# 164_001_01B-v2.net
KiCad netlist of a schematic drawn in EAGLE
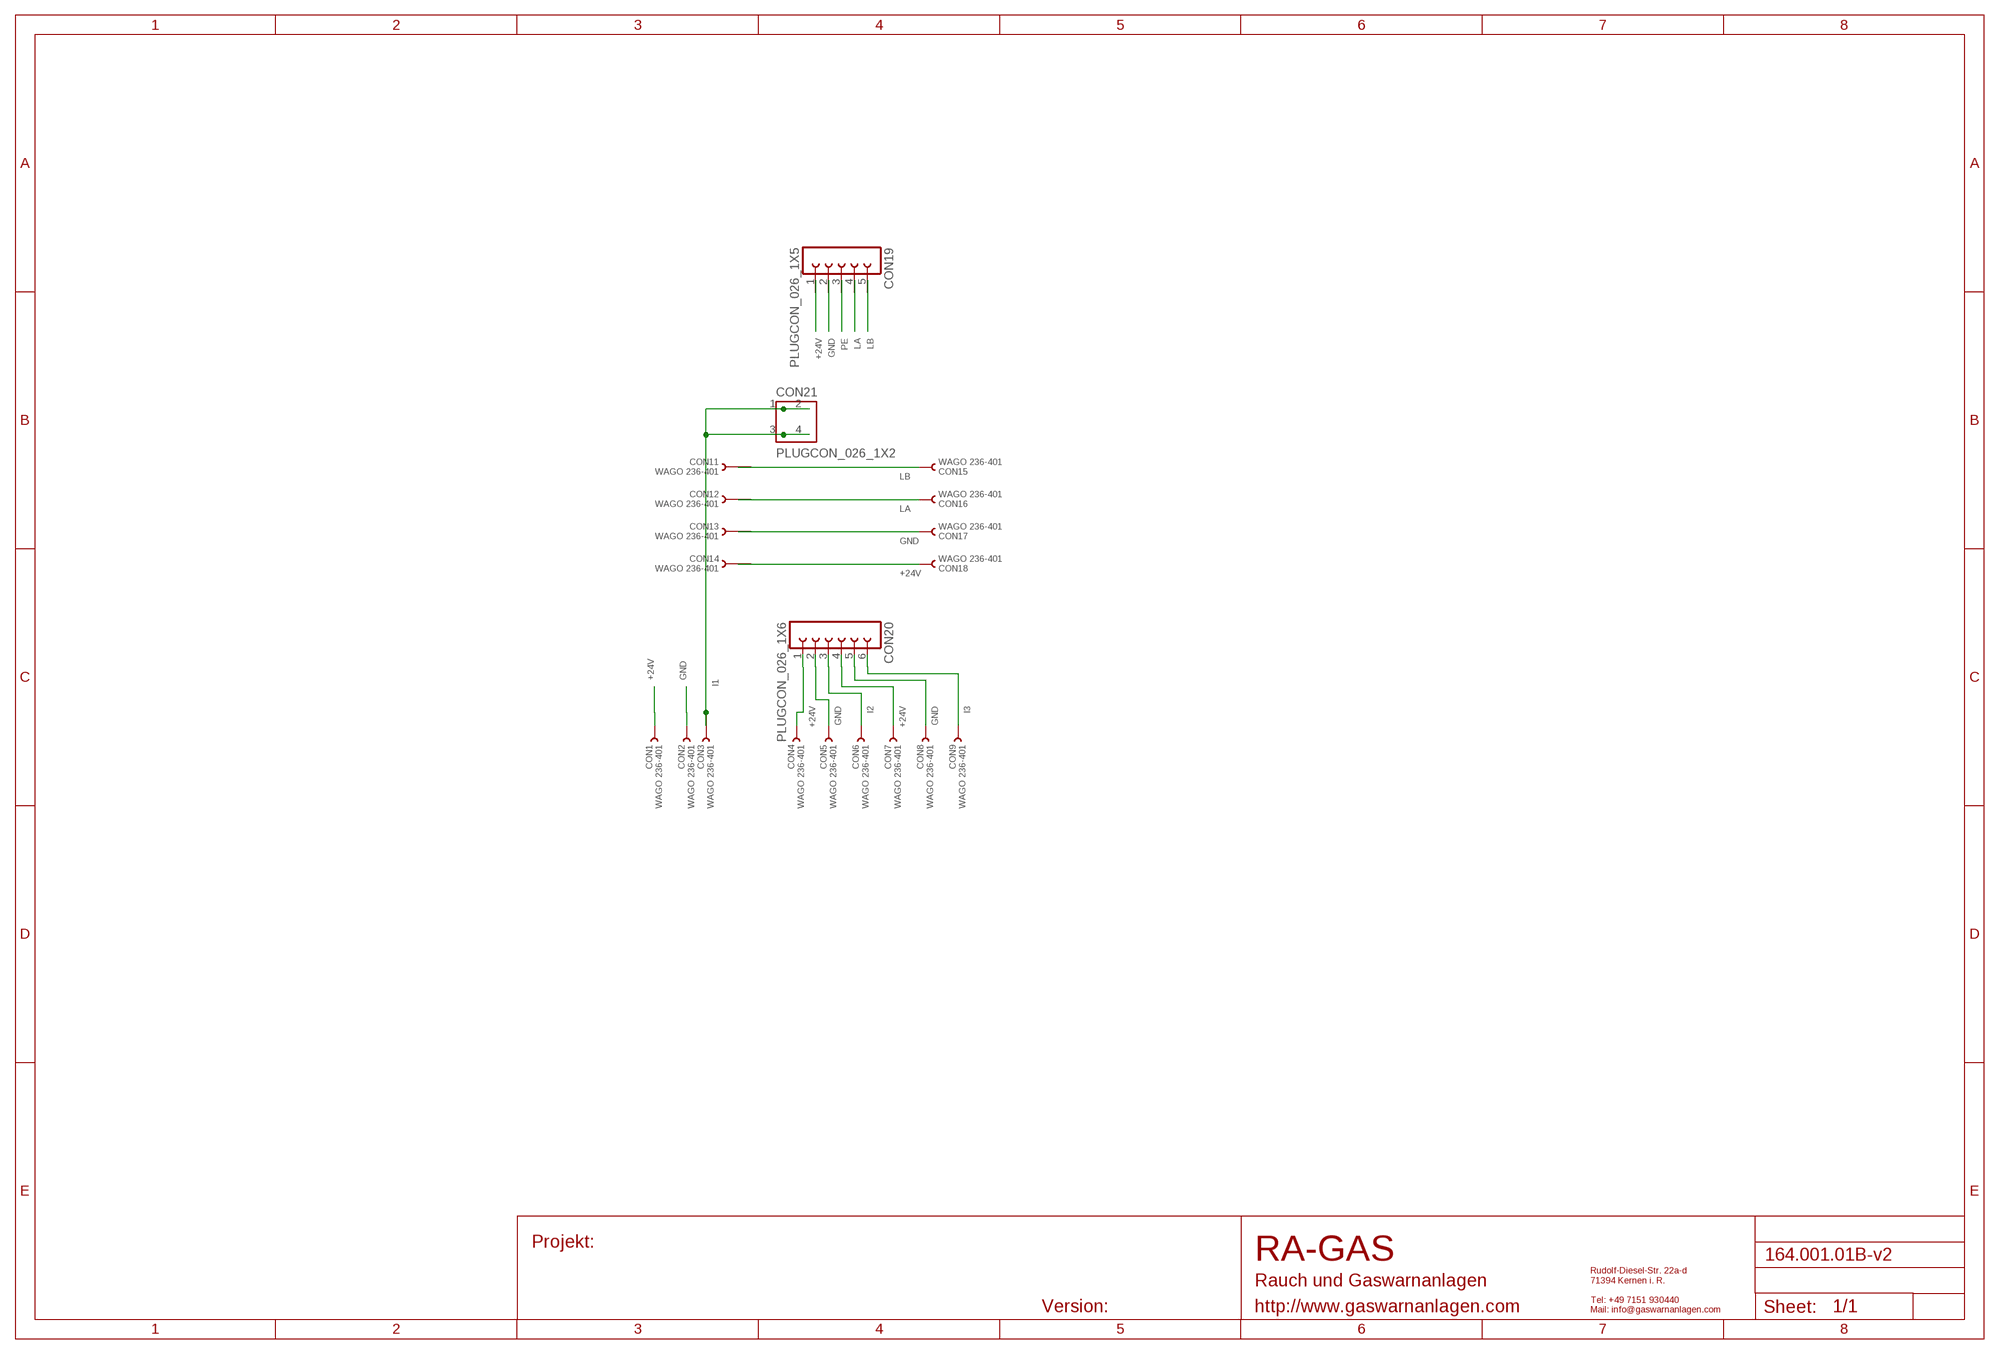
[diagram p0: schematic, sheet 1]

(export (version "E")
  (design (tool "Eeschema 10.0.6"))
  (components
    (comp (ref "CON1")
      (value "WAGO 236-401")
      (footprint "eagle-import:WAGO236")
      (libsource (lib "eagle-import") (part "RK1_WAGO236"))
    )
    (comp (ref "CON2")
      (value "WAGO 236-401")
      (footprint "eagle-import:WAGO236")
      (libsource (lib "eagle-import") (part "RK1_WAGO236"))
    )
    (comp (ref "CON3")
      (value "WAGO 236-401")
      (footprint "eagle-import:WAGO236")
      (libsource (lib "eagle-import") (part "RK1_WAGO236"))
    )
    (comp (ref "CON4")
      (value "WAGO 236-401")
      (footprint "eagle-import:WAGO236")
      (libsource (lib "eagle-import") (part "RK1_WAGO236"))
    )
    (comp (ref "CON5")
      (value "WAGO 236-401")
      (footprint "eagle-import:WAGO236")
      (libsource (lib "eagle-import") (part "RK1_WAGO236"))
    )
    (comp (ref "CON6")
      (value "WAGO 236-401")
      (footprint "eagle-import:WAGO236")
      (libsource (lib "eagle-import") (part "RK1_WAGO236"))
    )
    (comp (ref "CON7")
      (value "WAGO 236-401")
      (footprint "eagle-import:WAGO236")
      (libsource (lib "eagle-import") (part "RK1_WAGO236"))
    )
    (comp (ref "CON8")
      (value "WAGO 236-401")
      (footprint "eagle-import:WAGO236")
      (libsource (lib "eagle-import") (part "RK1_WAGO236"))
    )
    (comp (ref "CON9")
      (value "WAGO 236-401")
      (footprint "eagle-import:WAGO236")
      (libsource (lib "eagle-import") (part "RK1_WAGO236"))
    )
    (comp (ref "CON11")
      (value "WAGO 236-401")
      (footprint "eagle-import:WAGO236")
      (libsource (lib "eagle-import") (part "RK1_WAGO236"))
    )
    (comp (ref "CON12")
      (value "WAGO 236-401")
      (footprint "eagle-import:WAGO236")
      (libsource (lib "eagle-import") (part "RK1_WAGO236"))
    )
    (comp (ref "CON13")
      (value "WAGO 236-401")
      (footprint "eagle-import:WAGO236")
      (libsource (lib "eagle-import") (part "RK1_WAGO236"))
    )
    (comp (ref "CON14")
      (value "WAGO 236-401")
      (footprint "eagle-import:WAGO236")
      (libsource (lib "eagle-import") (part "RK1_WAGO236"))
    )
    (comp (ref "CON15")
      (value "WAGO 236-401")
      (footprint "eagle-import:WAGO236")
      (libsource (lib "eagle-import") (part "RK1_WAGO236"))
    )
    (comp (ref "CON16")
      (value "WAGO 236-401")
      (footprint "eagle-import:WAGO236")
      (libsource (lib "eagle-import") (part "RK1_WAGO236"))
    )
    (comp (ref "CON17")
      (value "WAGO 236-401")
      (footprint "eagle-import:WAGO236")
      (libsource (lib "eagle-import") (part "RK1_WAGO236"))
    )
    (comp (ref "CON18")
      (value "WAGO 236-401")
      (footprint "eagle-import:WAGO236")
      (libsource (lib "eagle-import") (part "RK1_WAGO236"))
    )
    (comp (ref "CON19")
      (value "PLUGCON_026_1X5")
      (footprint "eagle-import:PLUGCON1X5")
      (libsource (lib "eagle-import") (part "PLUGCON_026_1X5"))
    )
    (comp (ref "CON20")
      (value "PLUGCON_026_1X6")
      (footprint "eagle-import:PLUGCON1X6")
      (libsource (lib "eagle-import") (part "PLUGCON_026_1X6"))
    )
    (comp (ref "CON21")
      (value "PLUGCON_026_1X2")
      (footprint "eagle-import:PLUGCON1X2")
      (libsource (lib "eagle-import") (part "PLUGCON_026_1X2"))
    )
  )
  (nets
    (net (code "1") (name "/+24V") (class "Default")
      (node (ref "CON1") (pin "1") (pinfunction "1_1") (pintype "passive"))
      (node (ref "CON1") (pin "2") (pinfunction "2_2") (pintype "passive"))
      (node (ref "CON14") (pin "1") (pinfunction "1_1") (pintype "passive"))
      (node (ref "CON14") (pin "2") (pinfunction "2_2") (pintype "passive"))
      (node (ref "CON18") (pin "1") (pinfunction "1_1") (pintype "passive"))
      (node (ref "CON18") (pin "2") (pinfunction "2_2") (pintype "passive"))
      (node (ref "CON19") (pin "1") (pinfunction "1_1") (pintype "bidirectional"))
      (node (ref "CON19") (pin "6") (pinfunction "6_6") (pintype "bidirectional"))
      (node (ref "CON20") (pin "1") (pinfunction "1_1") (pintype "bidirectional"))
      (node (ref "CON20") (pin "10") (pinfunction "10_10") (pintype "bidirectional"))
      (node (ref "CON20") (pin "4") (pinfunction "4_4") (pintype "bidirectional"))
      (node (ref "CON20") (pin "7") (pinfunction "7_7") (pintype "bidirectional"))
      (node (ref "CON4") (pin "1") (pinfunction "1_1") (pintype "passive"))
      (node (ref "CON4") (pin "2") (pinfunction "2_2") (pintype "passive"))
      (node (ref "CON7") (pin "1") (pinfunction "1_1") (pintype "passive"))
      (node (ref "CON7") (pin "2") (pinfunction "2_2") (pintype "passive"))
    )
    (net (code "2") (name "/GND") (class "Default")
      (node (ref "CON13") (pin "1") (pinfunction "1_1") (pintype "passive"))
      (node (ref "CON13") (pin "2") (pinfunction "2_2") (pintype "passive"))
      (node (ref "CON17") (pin "1") (pinfunction "1_1") (pintype "passive"))
      (node (ref "CON17") (pin "2") (pinfunction "2_2") (pintype "passive"))
      (node (ref "CON19") (pin "2") (pinfunction "2_2") (pintype "bidirectional"))
      (node (ref "CON19") (pin "7") (pinfunction "7_7") (pintype "bidirectional"))
      (node (ref "CON2") (pin "1") (pinfunction "1_1") (pintype "passive"))
      (node (ref "CON2") (pin "2") (pinfunction "2_2") (pintype "passive"))
      (node (ref "CON20") (pin "11") (pinfunction "11_11") (pintype "bidirectional"))
      (node (ref "CON20") (pin "2") (pinfunction "2_2") (pintype "bidirectional"))
      (node (ref "CON20") (pin "5") (pinfunction "5_5") (pintype "bidirectional"))
      (node (ref "CON20") (pin "8") (pinfunction "8_8") (pintype "bidirectional"))
      (node (ref "CON5") (pin "1") (pinfunction "1_1") (pintype "passive"))
      (node (ref "CON5") (pin "2") (pinfunction "2_2") (pintype "passive"))
      (node (ref "CON8") (pin "1") (pinfunction "1_1") (pintype "passive"))
      (node (ref "CON8") (pin "2") (pinfunction "2_2") (pintype "passive"))
    )
    (net (code "3") (name "/I1") (class "Default")
      (node (ref "CON21") (pin "1") (pinfunction "1_1") (pintype "passive"))
      (node (ref "CON21") (pin "2") (pinfunction "1_2") (pintype "passive"))
      (node (ref "CON21") (pin "3") (pinfunction "2_3") (pintype "passive"))
      (node (ref "CON21") (pin "4") (pinfunction "2_4") (pintype "passive"))
      (node (ref "CON3") (pin "1") (pinfunction "1_1") (pintype "passive"))
      (node (ref "CON3") (pin "2") (pinfunction "2_2") (pintype "passive"))
    )
    (net (code "4") (name "/I2") (class "Default")
      (node (ref "CON20") (pin "3") (pinfunction "3_3") (pintype "bidirectional"))
      (node (ref "CON20") (pin "9") (pinfunction "9_9") (pintype "bidirectional"))
      (node (ref "CON6") (pin "1") (pinfunction "1_1") (pintype "passive"))
      (node (ref "CON6") (pin "2") (pinfunction "2_2") (pintype "passive"))
    )
    (net (code "5") (name "/I3") (class "Default")
      (node (ref "CON20") (pin "12") (pinfunction "12_12") (pintype "bidirectional"))
      (node (ref "CON20") (pin "6") (pinfunction "6_6") (pintype "bidirectional"))
      (node (ref "CON9") (pin "1") (pinfunction "1_1") (pintype "passive"))
      (node (ref "CON9") (pin "2") (pinfunction "2_2") (pintype "passive"))
    )
    (net (code "6") (name "/LA") (class "Default")
      (node (ref "CON12") (pin "1") (pinfunction "1_1") (pintype "passive"))
      (node (ref "CON12") (pin "2") (pinfunction "2_2") (pintype "passive"))
      (node (ref "CON16") (pin "1") (pinfunction "1_1") (pintype "passive"))
      (node (ref "CON16") (pin "2") (pinfunction "2_2") (pintype "passive"))
      (node (ref "CON19") (pin "4") (pinfunction "4_4") (pintype "bidirectional"))
      (node (ref "CON19") (pin "9") (pinfunction "9_9") (pintype "bidirectional"))
    )
    (net (code "7") (name "/LB") (class "Default")
      (node (ref "CON11") (pin "1") (pinfunction "1_1") (pintype "passive"))
      (node (ref "CON11") (pin "2") (pinfunction "2_2") (pintype "passive"))
      (node (ref "CON15") (pin "1") (pinfunction "1_1") (pintype "passive"))
      (node (ref "CON15") (pin "2") (pinfunction "2_2") (pintype "passive"))
      (node (ref "CON19") (pin "10") (pinfunction "10_10") (pintype "bidirectional"))
      (node (ref "CON19") (pin "5") (pinfunction "5_5") (pintype "bidirectional"))
    )
    (net (code "8") (name "/PE") (class "Default")
      (node (ref "CON19") (pin "3") (pinfunction "3_3") (pintype "bidirectional"))
      (node (ref "CON19") (pin "8") (pinfunction "8_8") (pintype "bidirectional"))
    )
  )
)
